# SuperTester-v08.net
KiCad netlist of a schematic drawn in EAGLE
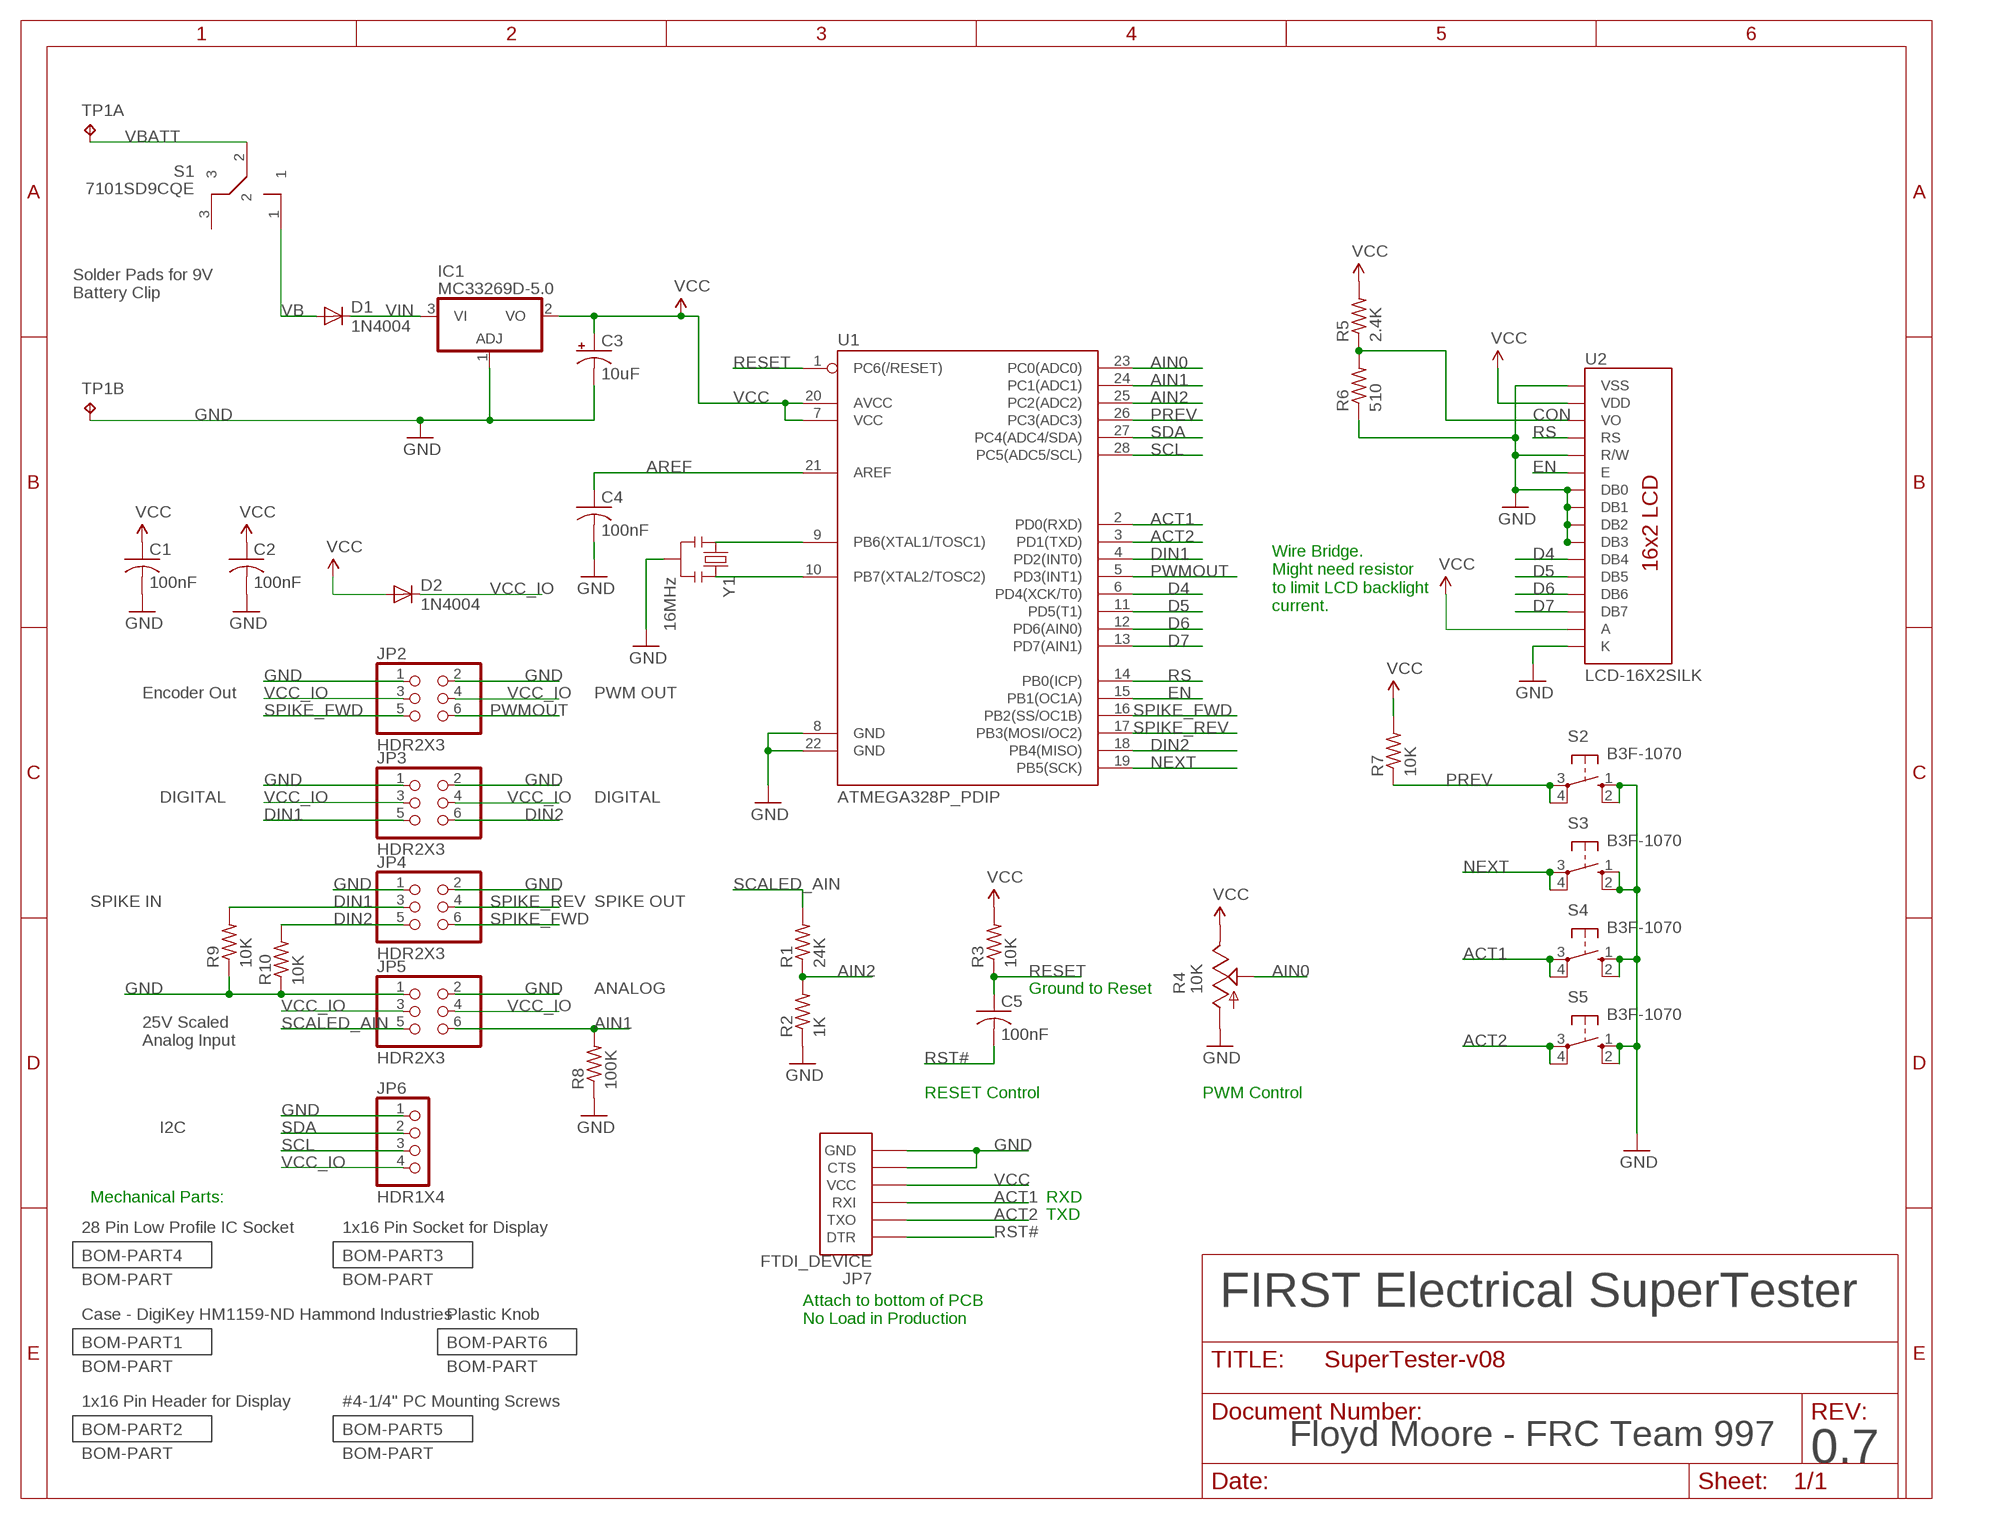
[diagram p0: schematic, sheet 1]

(export (version "E")
  (design (tool "Eeschema 10.0.6"))
  (components
    (comp (ref "C1")
      (value "100nF")
      (footprint "eagle-import:C025-025X050")
      (fields (field (name "PARTNO") "SR295E104MAR"))
      (libsource (lib "eagle-import") (part "C-US025-025X050"))
    )
    (comp (ref "C2")
      (value "100nF")
      (footprint "eagle-import:C025-025X050")
      (fields (field (name "PARTNO") "SR295E104MAR"))
      (libsource (lib "eagle-import") (part "C-US025-025X050"))
    )
    (comp (ref "C3")
      (value "10uF")
      (footprint "eagle-import:E2,5-6E")
      (fields (field (name "PARTNO") "TAP106M025SCS"))
      (libsource (lib "eagle-import") (part "CPOL-USE2,5-6E"))
    )
    (comp (ref "C4")
      (value "100nF")
      (footprint "eagle-import:C025-025X050")
      (fields (field (name "PARTNO") "SR295E104MAR"))
      (libsource (lib "eagle-import") (part "C-US025-025X050"))
    )
    (comp (ref "C5")
      (value "100nF")
      (footprint "eagle-import:C025-025X050")
      (fields (field (name "PARTNO") "SR295E104MAR"))
      (libsource (lib "eagle-import") (part "C-US025-025X050"))
    )
    (comp (ref "D1")
      (value "1N4004")
      (footprint "eagle-import:DO41-10")
      (fields (field (name "PARTNO") "1N4004GP-E3/54"))
      (libsource (lib "eagle-import") (part "1N4004"))
    )
    (comp (ref "D2")
      (value "1N4004")
      (footprint "eagle-import:DO41-10")
      (fields (field (name "PARTNO") "1N4004GP-E3/54"))
      (libsource (lib "eagle-import") (part "1N4004"))
    )
    (comp (ref "IC1")
      (value "MC33269D-5.0")
      (footprint "eagle-import:DPACK")
      (fields (field (name "PARTNO") "MC33269DTRK-5.0G"))
      (libsource (lib "eagle-import") (part "MC33269?D-5.0"))
    )
    (comp (ref "JP2")
      (value "HDR2X3")
      (footprint "eagle-import:2X03_90")
      (fields (field (name "PARTNO") "68021-206HLF"))
      (libsource (lib "eagle-import") (part "PINHD-2X3/90"))
    )
    (comp (ref "JP3")
      (value "HDR2X3")
      (footprint "eagle-import:2X03_90")
      (fields (field (name "PARTNO") "68021-206HLF"))
      (libsource (lib "eagle-import") (part "PINHD-2X3/90"))
    )
    (comp (ref "JP4")
      (value "HDR2X3")
      (footprint "eagle-import:2X03_90")
      (fields (field (name "PARTNO") "68021-206HLF"))
      (libsource (lib "eagle-import") (part "PINHD-2X3/90"))
    )
    (comp (ref "JP5")
      (value "HDR2X3")
      (footprint "eagle-import:2X03_90")
      (fields (field (name "PARTNO") "68021-206HLF"))
      (libsource (lib "eagle-import") (part "PINHD-2X3/90"))
    )
    (comp (ref "JP6")
      (value "HDR1X4")
      (footprint "eagle-import:1X04_90")
      (fields (field (name "PARTNO") "68016-204HLF"))
      (libsource (lib "eagle-import") (part "PINHD-1X4/90"))
    )
    (comp (ref "JP7")
      (value "FTDI_DEVICE")
      (footprint "eagle-import:FTDI_DEVICE_SIDE")
      (fields (field (name "PARTNO") "825437-6"))
      (libsource (lib "eagle-import") (part "FTDI_DEVICE"))
    )
    (comp (ref "R1")
      (value "24K")
      (footprint "eagle-import:0207_7")
      (fields (field (name "PARTNO") "CFR-12JB-52-24K"))
      (libsource (lib "eagle-import") (part "R-US_0207/7"))
    )
    (comp (ref "R2")
      (value "1K")
      (footprint "eagle-import:0207_7")
      (fields (field (name "PARTNO") "CFR-12JB-52-1K"))
      (libsource (lib "eagle-import") (part "R-US_0207/7"))
    )
    (comp (ref "R3")
      (value "10K")
      (footprint "eagle-import:0207_7")
      (fields (field (name "PARTNO") "CFR-12JB-52-10K"))
      (libsource (lib "eagle-import") (part "R-US_0207/7"))
    )
    (comp (ref "R4")
      (value "10K")
      (footprint "eagle-import:EVUF")
      (fields (field (name "PARTNO") "EVU-F3AF30B14"))
      (libsource (lib "eagle-import") (part "US-EVUAF3"))
    )
    (comp (ref "R5")
      (value "2.4K")
      (footprint "eagle-import:0207_7")
      (fields (field (name "PARTNO") "CFR-12JB-52-2K4"))
      (libsource (lib "eagle-import") (part "R-US_0207/7"))
    )
    (comp (ref "R6")
      (value "510")
      (footprint "eagle-import:0207_7")
      (fields (field (name "PARTNO") "CFR-12JB-52-510R"))
      (libsource (lib "eagle-import") (part "R-US_0207/7"))
    )
    (comp (ref "R7")
      (value "10K")
      (footprint "eagle-import:0207_7")
      (fields (field (name "PARTNO") "CFR-12JB-52-10K"))
      (libsource (lib "eagle-import") (part "R-US_0207/7"))
    )
    (comp (ref "R8")
      (value "100K")
      (footprint "eagle-import:0207_7")
      (fields (field (name "PARTNO") "CFR-12JB-52-100K"))
      (libsource (lib "eagle-import") (part "R-US_0207/7"))
    )
    (comp (ref "R9")
      (value "10K")
      (footprint "eagle-import:0207_7")
      (fields (field (name "PARTNO") "CFR-12JB-52-10K"))
      (libsource (lib "eagle-import") (part "R-US_0207/7"))
    )
    (comp (ref "R10")
      (value "10K")
      (footprint "eagle-import:0207_7")
      (fields (field (name "PARTNO") "CFR-12JB-52-10K"))
      (libsource (lib "eagle-import") (part "R-US_0207/7"))
    )
    (comp (ref "S1")
      (value "7101SD9CQE")
      (footprint "eagle-import:CK7101SD9CQE")
      (libsource (lib "eagle-import") (part "CK7101CK7101"))
    )
    (comp (ref "S2")
      (value "B3F-1070")
      (footprint "eagle-import:B3F-10XX")
      (fields (field (name "MPN") "B3F-1000"))
      (libsource (lib "eagle-import") (part "10-XX"))
    )
    (comp (ref "S3")
      (value "B3F-1070")
      (footprint "eagle-import:B3F-10XX")
      (fields (field (name "MPN") "B3F-1000"))
      (libsource (lib "eagle-import") (part "10-XX"))
    )
    (comp (ref "S4")
      (value "B3F-1070")
      (footprint "eagle-import:B3F-10XX")
      (fields (field (name "MPN") "B3F-1000"))
      (libsource (lib "eagle-import") (part "10-XX"))
    )
    (comp (ref "S5")
      (value "B3F-1070")
      (footprint "eagle-import:B3F-10XX")
      (fields (field (name "MPN") "B3F-1000"))
      (libsource (lib "eagle-import") (part "10-XX"))
    )
    (comp (ref "TP1")
      (value "TP2P2-38-20")
      (footprint "eagle-import:P2-38-20")
      (fields (field (name "BOM") "EXCLUDE"))
      (libsource (lib "eagle-import") (part "TP2P2-38-20"))
    )
    (comp (ref "U1")
      (value "ATMEGA328P_PDIP")
      (footprint "eagle-import:DIL28-3")
      (fields (field (name "PARTNO") "ATMEGA328P-PU"))
      (libsource (lib "eagle-import") (part "ATMEGA328P_PDIP"))
    )
    (comp (ref "U2")
      (value "LCD-16X2SILK")
      (footprint "eagle-import:LCD-16X2")
      (fields (field (name "PARTNO") "LCM-S01602DSF/A"))
      (libsource (lib "eagle-import") (part "LCD-16X2SILK"))
    )
    (comp (ref "Y1")
      (value "16MHz")
      (footprint "eagle-import:RESONATOR-PTH")
      (fields (field (name "PARTNO") "CSTLS16M0X53-B0"))
      (libsource (lib "eagle-import") (part "RESONATORPTH"))
    )
  )
  (nets
    (net (code "1") (name "/ACT1") (class "Default")
      (node (ref "JP7") (pin "P$3") (pinfunction "RXI_P$3") (pintype "bidirectional"))
      (node (ref "S4") (pin "3") (pinfunction "P_3") (pintype "passive"))
      (node (ref "S4") (pin "4") (pinfunction "P1_4") (pintype "passive"))
      (node (ref "U1") (pin "2") (pinfunction "PD0(RXD)_2") (pintype "bidirectional"))
    )
    (net (code "2") (name "/ACT2") (class "Default")
      (node (ref "JP7") (pin "P$2") (pinfunction "TXO_P$2") (pintype "bidirectional"))
      (node (ref "S5") (pin "3") (pinfunction "P_3") (pintype "passive"))
      (node (ref "S5") (pin "4") (pinfunction "P1_4") (pintype "passive"))
      (node (ref "U1") (pin "3") (pinfunction "PD1(TXD)_3") (pintype "bidirectional"))
    )
    (net (code "3") (name "/AIN0") (class "Default")
      (node (ref "R4") (pin "2") (pinfunction "S_2") (pintype "passive"))
      (node (ref "U1") (pin "23") (pinfunction "PC0(ADC0)_23") (pintype "bidirectional"))
    )
    (net (code "4") (name "/AIN1") (class "Default")
      (node (ref "JP5") (pin "6") (pinfunction "6_6") (pintype "passive"))
      (node (ref "R8") (pin "2") (pinfunction "2_2") (pintype "passive"))
      (node (ref "U1") (pin "24") (pinfunction "PC1(ADC1)_24") (pintype "bidirectional"))
    )
    (net (code "5") (name "/AIN2") (class "Default")
      (node (ref "R1") (pin "1") (pinfunction "1_1") (pintype "passive"))
      (node (ref "R2") (pin "2") (pinfunction "2_2") (pintype "passive"))
      (node (ref "U1") (pin "25") (pinfunction "PC2(ADC2)_25") (pintype "bidirectional"))
    )
    (net (code "6") (name "/AREF") (class "Default")
      (node (ref "C4") (pin "1") (pinfunction "1_1") (pintype "passive"))
      (node (ref "U1") (pin "21") (pinfunction "AREF_21") (pintype "bidirectional"))
    )
    (net (code "7") (name "/CON") (class "Default")
      (node (ref "R5") (pin "1") (pinfunction "1_1") (pintype "passive"))
      (node (ref "R6") (pin "2") (pinfunction "2_2") (pintype "passive"))
      (node (ref "U2") (pin "3") (pinfunction "VO_3") (pintype "bidirectional"))
    )
    (net (code "8") (name "/D4") (class "Default")
      (node (ref "U1") (pin "6") (pinfunction "PD4(XCK/T0)_6") (pintype "bidirectional"))
      (node (ref "U2") (pin "11") (pinfunction "DB4_11") (pintype "bidirectional"))
    )
    (net (code "9") (name "/D5") (class "Default")
      (node (ref "U1") (pin "11") (pinfunction "PD5(T1)_11") (pintype "bidirectional"))
      (node (ref "U2") (pin "12") (pinfunction "DB5_12") (pintype "bidirectional"))
    )
    (net (code "10") (name "/D6") (class "Default")
      (node (ref "U1") (pin "12") (pinfunction "PD6(AIN0)_12") (pintype "bidirectional"))
      (node (ref "U2") (pin "13") (pinfunction "DB6_13") (pintype "bidirectional"))
    )
    (net (code "11") (name "/D7") (class "Default")
      (node (ref "U1") (pin "13") (pinfunction "PD7(AIN1)_13") (pintype "bidirectional"))
      (node (ref "U2") (pin "14") (pinfunction "DB7_14") (pintype "bidirectional"))
    )
    (net (code "12") (name "/DIN1") (class "Default")
      (node (ref "JP3") (pin "5") (pinfunction "5_5") (pintype "passive"))
      (node (ref "JP4") (pin "3") (pinfunction "3_3") (pintype "passive"))
      (node (ref "R9") (pin "2") (pinfunction "2_2") (pintype "passive"))
      (node (ref "U1") (pin "4") (pinfunction "PD2(INT0)_4") (pintype "bidirectional"))
    )
    (net (code "13") (name "/DIN2") (class "Default")
      (node (ref "JP3") (pin "6") (pinfunction "6_6") (pintype "passive"))
      (node (ref "JP4") (pin "5") (pinfunction "5_5") (pintype "passive"))
      (node (ref "R10") (pin "2") (pinfunction "2_2") (pintype "passive"))
      (node (ref "U1") (pin "18") (pinfunction "PB4(MISO)_18") (pintype "bidirectional"))
    )
    (net (code "14") (name "/EN") (class "Default")
      (node (ref "U1") (pin "15") (pinfunction "PB1(OC1A)_15") (pintype "bidirectional"))
      (node (ref "U2") (pin "6") (pinfunction "E_6") (pintype "input"))
    )
    (net (code "15") (name "/NEXT") (class "Default")
      (node (ref "S3") (pin "3") (pinfunction "P_3") (pintype "passive"))
      (node (ref "S3") (pin "4") (pinfunction "P1_4") (pintype "passive"))
      (node (ref "U1") (pin "19") (pinfunction "PB5(SCK)_19") (pintype "bidirectional"))
    )
    (net (code "16") (name "/PREV") (class "Default")
      (node (ref "R7") (pin "1") (pinfunction "1_1") (pintype "passive"))
      (node (ref "S2") (pin "3") (pinfunction "P_3") (pintype "passive"))
      (node (ref "S2") (pin "4") (pinfunction "P1_4") (pintype "passive"))
      (node (ref "U1") (pin "26") (pinfunction "PC3(ADC3)_26") (pintype "bidirectional"))
    )
    (net (code "17") (name "/PWMOUT") (class "Default")
      (node (ref "JP2") (pin "6") (pinfunction "6_6") (pintype "passive"))
      (node (ref "U1") (pin "5") (pinfunction "PD3(INT1)_5") (pintype "bidirectional"))
    )
    (net (code "18") (name "/RESET") (class "Default")
      (node (ref "C5") (pin "1") (pinfunction "1_1") (pintype "passive"))
      (node (ref "R3") (pin "1") (pinfunction "1_1") (pintype "passive"))
      (node (ref "U1") (pin "1") (pinfunction "PC6(/RESET)_1") (pintype "bidirectional"))
    )
    (net (code "19") (name "/RS") (class "Default")
      (node (ref "U1") (pin "14") (pinfunction "PB0(ICP)_14") (pintype "bidirectional"))
      (node (ref "U2") (pin "4") (pinfunction "RS_4") (pintype "input"))
    )
    (net (code "20") (name "/RST#") (class "Default")
      (node (ref "C5") (pin "2") (pinfunction "2_2") (pintype "passive"))
      (node (ref "JP7") (pin "P$1") (pinfunction "DTR_P$1") (pintype "bidirectional"))
    )
    (net (code "21") (name "/SCALED_AIN") (class "Default")
      (node (ref "JP5") (pin "5") (pinfunction "5_5") (pintype "passive"))
      (node (ref "R1") (pin "2") (pinfunction "2_2") (pintype "passive"))
    )
    (net (code "22") (name "/SCL") (class "Default")
      (node (ref "JP6") (pin "3") (pinfunction "3_3") (pintype "passive"))
      (node (ref "U1") (pin "28") (pinfunction "PC5(ADC5/SCL)_28") (pintype "bidirectional"))
    )
    (net (code "23") (name "/SDA") (class "Default")
      (node (ref "JP6") (pin "2") (pinfunction "2_2") (pintype "passive"))
      (node (ref "U1") (pin "27") (pinfunction "PC4(ADC4/SDA)_27") (pintype "bidirectional"))
    )
    (net (code "24") (name "/SPIKE_FWD") (class "Default")
      (node (ref "JP2") (pin "5") (pinfunction "5_5") (pintype "passive"))
      (node (ref "JP4") (pin "6") (pinfunction "6_6") (pintype "passive"))
      (node (ref "U1") (pin "16") (pinfunction "PB2(SS/OC1B)_16") (pintype "bidirectional"))
    )
    (net (code "25") (name "/SPIKE_REV") (class "Default")
      (node (ref "JP4") (pin "4") (pinfunction "4_4") (pintype "passive"))
      (node (ref "U1") (pin "17") (pinfunction "PB3(MOSI/OC2)_17") (pintype "bidirectional"))
    )
    (net (code "26") (name "/VB") (class "Default")
      (node (ref "D1") (pin "A") (pinfunction "A_A") (pintype "passive"))
      (node (ref "S1") (pin "1") (pinfunction "1_1") (pintype "bidirectional"))
    )
    (net (code "27") (name "/VBATT") (class "Default")
      (node (ref "S1") (pin "2") (pinfunction "2_2") (pintype "bidirectional"))
      (node (ref "TP1") (pin "TP-1") (pinfunction "TP_TP-1") (pintype "input"))
    )
    (net (code "28") (name "/VCC_IO") (class "Default")
      (node (ref "D2") (pin "C") (pinfunction "C_C") (pintype "passive"))
      (node (ref "JP2") (pin "3") (pinfunction "3_3") (pintype "passive"))
      (node (ref "JP2") (pin "4") (pinfunction "4_4") (pintype "passive"))
      (node (ref "JP3") (pin "3") (pinfunction "3_3") (pintype "passive"))
      (node (ref "JP3") (pin "4") (pinfunction "4_4") (pintype "passive"))
      (node (ref "JP5") (pin "3") (pinfunction "3_3") (pintype "passive"))
      (node (ref "JP5") (pin "4") (pinfunction "4_4") (pintype "passive"))
      (node (ref "JP6") (pin "4") (pinfunction "4_4") (pintype "passive"))
    )
    (net (code "29") (name "/VIN") (class "Default")
      (node (ref "D1") (pin "C") (pinfunction "C_C") (pintype "passive"))
      (node (ref "IC1") (pin "3") (pinfunction "VI_3") (pintype "input"))
    )
    (net (code "30") (name "GND") (class "Default")
      (node (ref "C1") (pin "2") (pinfunction "2_2") (pintype "passive"))
      (node (ref "C2") (pin "2") (pinfunction "2_2") (pintype "passive"))
      (node (ref "C3") (pin "-") (pinfunction "-_-") (pintype "passive"))
      (node (ref "C4") (pin "2") (pinfunction "2_2") (pintype "passive"))
      (node (ref "IC1") (pin "1") (pinfunction "ADJ_1") (pintype "input"))
      (node (ref "JP2") (pin "1") (pinfunction "1_1") (pintype "passive"))
      (node (ref "JP2") (pin "2") (pinfunction "2_2") (pintype "passive"))
      (node (ref "JP3") (pin "1") (pinfunction "1_1") (pintype "passive"))
      (node (ref "JP3") (pin "2") (pinfunction "2_2") (pintype "passive"))
      (node (ref "JP4") (pin "1") (pinfunction "1_1") (pintype "passive"))
      (node (ref "JP4") (pin "2") (pinfunction "2_2") (pintype "passive"))
      (node (ref "JP5") (pin "1") (pinfunction "1_1") (pintype "passive"))
      (node (ref "JP5") (pin "2") (pinfunction "2_2") (pintype "passive"))
      (node (ref "JP6") (pin "1") (pinfunction "1_1") (pintype "passive"))
      (node (ref "JP7") (pin "P$5") (pinfunction "CTS_P$5") (pintype "bidirectional"))
      (node (ref "JP7") (pin "P$6") (pinfunction "GND_P$6") (pintype "bidirectional"))
      (node (ref "R10") (pin "1") (pinfunction "1_1") (pintype "passive"))
      (node (ref "R2") (pin "1") (pinfunction "1_1") (pintype "passive"))
      (node (ref "R4") (pin "1") (pinfunction "A_1") (pintype "passive"))
      (node (ref "R6") (pin "1") (pinfunction "1_1") (pintype "passive"))
      (node (ref "R8") (pin "1") (pinfunction "1_1") (pintype "passive"))
      (node (ref "R9") (pin "1") (pinfunction "1_1") (pintype "passive"))
      (node (ref "S2") (pin "1") (pinfunction "S_1") (pintype "passive"))
      (node (ref "S2") (pin "2") (pinfunction "S1_2") (pintype "passive"))
      (node (ref "S3") (pin "1") (pinfunction "S_1") (pintype "passive"))
      (node (ref "S3") (pin "2") (pinfunction "S1_2") (pintype "passive"))
      (node (ref "S4") (pin "1") (pinfunction "S_1") (pintype "passive"))
      (node (ref "S4") (pin "2") (pinfunction "S1_2") (pintype "passive"))
      (node (ref "S5") (pin "1") (pinfunction "S_1") (pintype "passive"))
      (node (ref "S5") (pin "2") (pinfunction "S1_2") (pintype "passive"))
      (node (ref "TP1") (pin "TP-2") (pinfunction "TP_TP-2") (pintype "input"))
      (node (ref "U1") (pin "22") (pinfunction "GND_22") (pintype "bidirectional"))
      (node (ref "U1") (pin "8") (pinfunction "GND_8") (pintype "bidirectional"))
      (node (ref "U2") (pin "1") (pinfunction "VSS_1") (pintype "power_in"))
      (node (ref "U2") (pin "10") (pinfunction "DB3_10") (pintype "bidirectional"))
      (node (ref "U2") (pin "16") (pinfunction "K_16") (pintype "power_in"))
      (node (ref "U2") (pin "5") (pinfunction "R/W_5") (pintype "input"))
      (node (ref "U2") (pin "7") (pinfunction "DB0_7") (pintype "bidirectional"))
      (node (ref "U2") (pin "8") (pinfunction "DB1_8") (pintype "bidirectional"))
      (node (ref "U2") (pin "9") (pinfunction "DB2_9") (pintype "bidirectional"))
      (node (ref "Y1") (pin "2") (pinfunction "2_2") (pintype "passive"))
    )
    (net (code "31") (name "Net-(U1-PB6(XTAL1{slash}TOSC1))") (class "Default")
      (node (ref "U1") (pin "9") (pinfunction "PB6(XTAL1/TOSC1)_9") (pintype "bidirectional"))
      (node (ref "Y1") (pin "1") (pinfunction "1_1") (pintype "passive"))
    )
    (net (code "32") (name "Net-(U1-PB7(XTAL2{slash}TOSC2))") (class "Default")
      (node (ref "U1") (pin "10") (pinfunction "PB7(XTAL2/TOSC2)_10") (pintype "bidirectional"))
      (node (ref "Y1") (pin "3") (pinfunction "3_3") (pintype "passive"))
    )
    (net (code "33") (name "VCC") (class "Default")
      (node (ref "C1") (pin "1") (pinfunction "1_1") (pintype "passive"))
      (node (ref "C2") (pin "1") (pinfunction "1_1") (pintype "passive"))
      (node (ref "C3") (pin "+") (pinfunction "+_+") (pintype "passive"))
      (node (ref "D2") (pin "A") (pinfunction "A_A") (pintype "passive"))
      (node (ref "IC1") (pin "2") (pinfunction "VO_2") (pintype "passive"))
      (node (ref "JP7") (pin "P$4") (pinfunction "VCC_P$4") (pintype "bidirectional"))
      (node (ref "R3") (pin "2") (pinfunction "2_2") (pintype "passive"))
      (node (ref "R4") (pin "3") (pinfunction "E_3") (pintype "passive"))
      (node (ref "R5") (pin "2") (pinfunction "2_2") (pintype "passive"))
      (node (ref "R7") (pin "2") (pinfunction "2_2") (pintype "passive"))
      (node (ref "U1") (pin "20") (pinfunction "AVCC_20") (pintype "bidirectional"))
      (node (ref "U1") (pin "7") (pinfunction "VCC_7") (pintype "bidirectional"))
      (node (ref "U2") (pin "15") (pinfunction "A_15") (pintype "power_in"))
      (node (ref "U2") (pin "2") (pinfunction "VDD_2") (pintype "power_in"))
    )
    (net (code "34") (name "unconnected-(S1-Pad3)") (class "Default")
      (node (ref "S1") (pin "3") (pinfunction "3_3") (pintype "bidirectional"))
    )
  )
)
